# SoC_Fan_Header.net
KiCad netlist of a schematic drawn in Altium Designer
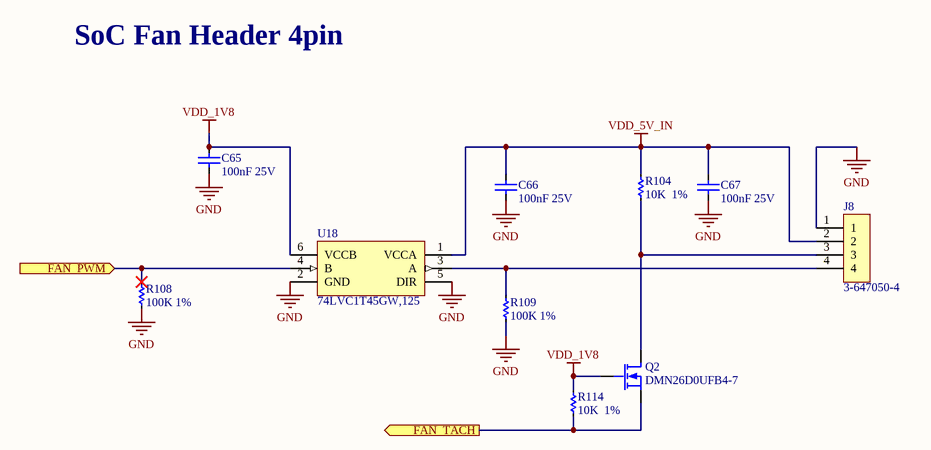
[diagram p0: SoC_Fan_Header.SchDoc]

(export (version "E")
  (design (tool "Eeschema 10.0.6"))
  (components
    (comp (ref "C65")
      (value "100nF 25V")
      (footprint "C0402")
      (description "CAP CER 0.1UF 25V X5R 0402 / High Value Multilayer Ceramic Capacitors (High dielectric type)")
      (fields
        (field (name "MANUFACTURER") "Taiyo Yuden")
        (field (name "MANUFACTURER PART NUMBER") "TMK105BJ104KV-F")
      )
      (libsource (lib "GM_Altium_Library") (part "TMK105BJ104KV-F"))
    )
    (comp (ref "C66")
      (value "100nF 25V")
      (footprint "C0402")
      (description "CAP CER 0.1UF 25V X5R 0402 / High Value Multilayer Ceramic Capacitors (High dielectric type)")
      (fields
        (field (name "MANUFACTURER") "Taiyo Yuden")
        (field (name "MANUFACTURER PART NUMBER") "TMK105BJ104KV-F")
      )
      (libsource (lib "GM_Altium_Library") (part "TMK105BJ104KV-F"))
    )
    (comp (ref "C67")
      (value "100nF 25V")
      (footprint "C0402")
      (description "CAP CER 0.1UF 25V X5R 0402 / High Value Multilayer Ceramic Capacitors (High dielectric type)")
      (fields
        (field (name "MANUFACTURER") "Taiyo Yuden")
        (field (name "MANUFACTURER PART NUMBER") "TMK105BJ104KV-F")
      )
      (libsource (lib "GM_Altium_Library") (part "TMK105BJ104KV-F"))
    )
    (comp (ref "J8")
      (value "3-647050-4")
      (footprint "3-647050-4")
      (description "Header Assembly 4 Position MTA100 F/L HITEMP MTA-100 Series")
      (fields (field (name "MANUFACTURER") "TE Connectivity"))
      (libsource (lib "GM_Altium_Library") (part "3-647050-4"))
    )
    (comp (ref "Q2")
      (value "DMN26D0UFB4-7")
      (footprint "DFN1006-3")
      (description "Single N-Channel 20 V 350 mW Silicon Surface Mount Mosfet - DFN-3")
      (fields (field (name "MANUFACTURER") "Diodes"))
      (libsource (lib "GM_Altium_Library") (part "DMN26D0UFB4-7"))
    )
    (comp (ref "R104")
      (value "10K  1%")
      (footprint "R0402")
      (description "Res General Purpose Thick Film 0402 10K Ohm 1% 1/16W ±100ppm/°C Molded SMD Paper T/R")
      (fields
        (field (name "MANUFACTURER") "Yageo")
        (field (name "MANUFACTURER PART NUMBER") "RC0402FR-0710KP")
      )
      (libsource (lib "GM_Altium_Library") (part "RC0402FR-0710KP"))
    )
    (comp (ref "R108")
      (value "100K 1%")
      (footprint "R0402")
      (description "RES SMD 100K OHM 1% 1/16W 0402")
      (fields
        (field (name "MANUFACTURER") "Yageo")
        (field (name "MANUFACTURER PART NUMBER") "RC0402FR-07100KL")
      )
      (libsource (lib "GM_Altium_Library") (part "RC0402FR-07100KL"))
    )
    (comp (ref "R109")
      (value "100K 1%")
      (footprint "R0402")
      (description "RES SMD 100K OHM 1% 1/16W 0402")
      (fields
        (field (name "MANUFACTURER") "Yageo")
        (field (name "MANUFACTURER PART NUMBER") "RC0402FR-07100KL")
      )
      (libsource (lib "GM_Altium_Library") (part "RC0402FR-07100KL"))
    )
    (comp (ref "R114")
      (value "10K  1%")
      (footprint "R0402")
      (description "Res General Purpose Thick Film 0402 10K Ohm 1% 1/16W ±100ppm/°C Molded SMD Paper T/R")
      (fields
        (field (name "MANUFACTURER") "Yageo")
        (field (name "MANUFACTURER PART NUMBER") "RC0402FR-0710KP")
      )
      (libsource (lib "GM_Altium_Library") (part "RC0402FR-0710KP"))
    )
    (comp (ref "U18")
      (value "74LVC1T45GW,125")
      (footprint "SOT-363")
      (description "TXRX XLATING DUAL 3ST 6TSSOP")
      (fields (field (name "MANUFACTURER") "Nexperia"))
      (libsource (lib "GM_Altium_Library") (part "74LVC1T45GW,125"))
    )
  )
  (nets
    (net (code "1") (name "/FAN_PWM") (class "Default")
      (node (ref "R108") (pin "2") (pinfunction "2_2") (pintype "passive"))
      (node (ref "U18") (pin "4") (pinfunction "B_4") (pintype "input"))
    )
    (net (code "2") (name "/FAN_TACH") (class "Default")
      (node (ref "Q2") (pin "2") (pinfunction "S_2") (pintype "passive"))
      (node (ref "R114") (pin "1") (pinfunction "1_1") (pintype "passive"))
    )
    (net (code "3") (name "GND") (class "Default")
      (node (ref "C65") (pin "1") (pinfunction "1_1") (pintype "passive"))
      (node (ref "C66") (pin "1") (pinfunction "1_1") (pintype "passive"))
      (node (ref "C67") (pin "1") (pinfunction "1_1") (pintype "passive"))
      (node (ref "J8") (pin "1") (pinfunction "1_1") (pintype "passive"))
      (node (ref "R108") (pin "1") (pinfunction "1_1") (pintype "passive"))
      (node (ref "R109") (pin "1") (pinfunction "1_1") (pintype "passive"))
      (node (ref "U18") (pin "2") (pinfunction "GND_2") (pintype "power_in"))
      (node (ref "U18") (pin "5") (pinfunction "DIR_5") (pintype "passive"))
    )
    (net (code "4") (name "Net-(Q2-D)") (class "Default")
      (node (ref "J8") (pin "3") (pinfunction "3_3") (pintype "passive"))
      (node (ref "Q2") (pin "3") (pinfunction "D_3") (pintype "passive"))
      (node (ref "R104") (pin "1") (pinfunction "1_1") (pintype "passive"))
    )
    (net (code "5") (name "Net-(U18-A)") (class "Default")
      (node (ref "J8") (pin "4") (pinfunction "4_4") (pintype "passive"))
      (node (ref "R109") (pin "2") (pinfunction "2_2") (pintype "passive"))
      (node (ref "U18") (pin "3") (pinfunction "A_3") (pintype "output"))
    )
    (net (code "6") (name "VDD_1V8") (class "Default")
      (node (ref "C65") (pin "2") (pinfunction "2_2") (pintype "passive"))
      (node (ref "Q2") (pin "1") (pinfunction "G_1") (pintype "passive"))
      (node (ref "R114") (pin "2") (pinfunction "2_2") (pintype "passive"))
      (node (ref "U18") (pin "6") (pinfunction "VCCB_6") (pintype "power_in"))
    )
    (net (code "7") (name "VDD_5V_IN") (class "Default")
      (node (ref "C66") (pin "2") (pinfunction "2_2") (pintype "passive"))
      (node (ref "C67") (pin "2") (pinfunction "2_2") (pintype "passive"))
      (node (ref "J8") (pin "2") (pinfunction "2_2") (pintype "passive"))
      (node (ref "R104") (pin "2") (pinfunction "2_2") (pintype "passive"))
      (node (ref "U18") (pin "1") (pinfunction "VCCA_1") (pintype "power_in"))
    )
  )
)
